# FRONT.net
KiCad netlist of a schematic drawn in Altium Designer
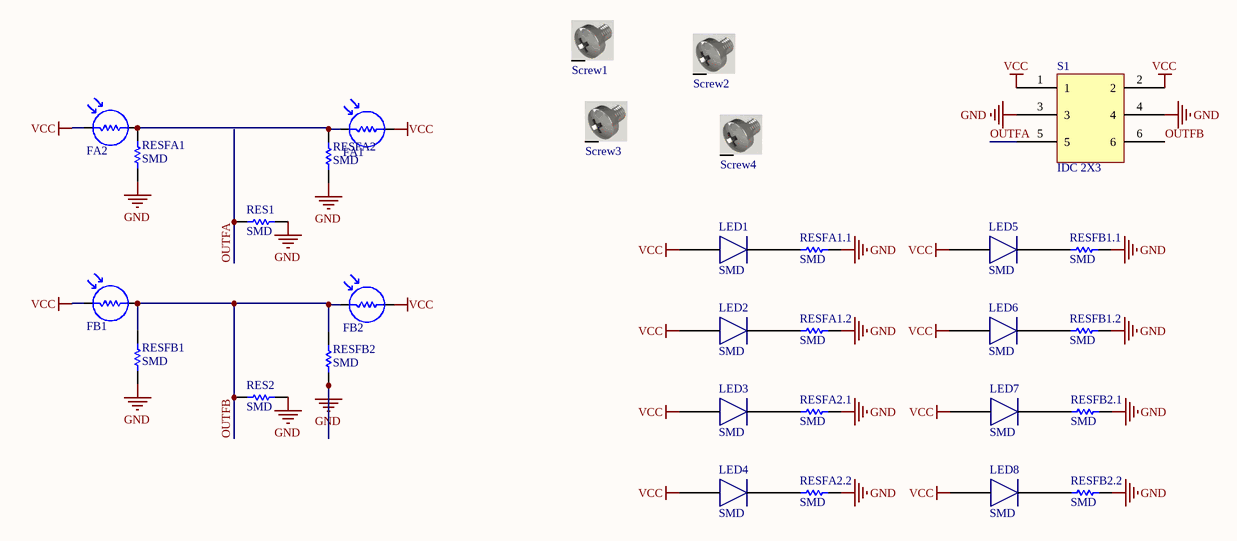
[diagram p0: FRONT.SchDoc]

(export (version "E")
  (design (tool "Eeschema 10.0.6"))
  (components
    (comp (ref "FA1")
      (value "Photo Cell")
      (footprint "PhotoCell.")
      (fields (field (name "PUBLISHER") "Altium Limited"))
      (libsource (lib "Farzanegan") (part "Photo Cell.."))
    )
    (comp (ref "FA2")
      (value "Photo Cell")
      (footprint "PhotoCell.")
      (fields (field (name "PUBLISHER") "Altium Limited"))
      (libsource (lib "Farzanegan") (part "Photo Cell.."))
    )
    (comp (ref "FB1")
      (value "Photo Cell")
      (footprint "PhotoCell.")
      (fields (field (name "PUBLISHER") "Altium Limited"))
      (libsource (lib "Farzanegan") (part "Photo Cell.."))
    )
    (comp (ref "FB2")
      (value "Photo Cell")
      (footprint "PhotoCell.")
      (fields (field (name "PUBLISHER") "Altium Limited"))
      (libsource (lib "Farzanegan") (part "Photo Cell.."))
    )
    (comp (ref "LED1") (value "SMD") (footprint "LED SMD") (libsource (lib "Farzanegan") (part "LED SMD")))
    (comp (ref "LED2") (value "SMD") (footprint "LED SMD") (libsource (lib "Farzanegan") (part "LED SMD")))
    (comp (ref "LED3") (value "SMD") (footprint "LED SMD") (libsource (lib "Farzanegan") (part "LED SMD")))
    (comp (ref "LED4") (value "SMD") (footprint "LED SMD") (libsource (lib "Farzanegan") (part "LED SMD")))
    (comp (ref "LED5") (value "SMD") (footprint "LED SMD") (libsource (lib "Farzanegan") (part "LED SMD")))
    (comp (ref "LED6") (value "SMD") (footprint "LED SMD") (libsource (lib "Farzanegan") (part "LED SMD")))
    (comp (ref "LED7") (value "SMD") (footprint "LED SMD") (libsource (lib "Farzanegan") (part "LED SMD")))
    (comp (ref "LED8") (value "SMD") (footprint "LED SMD") (libsource (lib "Farzanegan") (part "LED SMD")))
    (comp (ref "RES1")
      (value "SMD")
      (footprint "Resistor SMD 1206")
      (libsource (lib "Farzanegan") (part "Res SMD"))
    )
    (comp (ref "RES2")
      (value "SMD")
      (footprint "Resistor SMD 1206")
      (libsource (lib "Farzanegan") (part "Res SMD"))
    )
    (comp (ref "RESFA1")
      (value "SMD")
      (footprint "Resistor SMD 1206")
      (libsource (lib "Farzanegan") (part "Res SMD"))
    )
    (comp (ref "RESFA1.1")
      (value "SMD")
      (footprint "Resistor SMD 1206")
      (libsource (lib "Farzanegan") (part "Res SMD"))
    )
    (comp (ref "RESFA1.2")
      (value "SMD")
      (footprint "Resistor SMD 1206")
      (libsource (lib "Farzanegan") (part "Res SMD"))
    )
    (comp (ref "RESFA2")
      (value "SMD")
      (footprint "Resistor SMD 1206")
      (libsource (lib "Farzanegan") (part "Res SMD"))
    )
    (comp (ref "RESFA2.1")
      (value "SMD")
      (footprint "Resistor SMD 1206")
      (libsource (lib "Farzanegan") (part "Res SMD"))
    )
    (comp (ref "RESFA2.2")
      (value "SMD")
      (footprint "Resistor SMD 1206")
      (libsource (lib "Farzanegan") (part "Res SMD"))
    )
    (comp (ref "RESFB1")
      (value "SMD")
      (footprint "Resistor SMD 1206")
      (libsource (lib "Farzanegan") (part "Res SMD"))
    )
    (comp (ref "RESFB1.1")
      (value "SMD")
      (footprint "Resistor SMD 1206")
      (libsource (lib "Farzanegan") (part "Res SMD"))
    )
    (comp (ref "RESFB1.2")
      (value "SMD")
      (footprint "Resistor SMD 1206")
      (libsource (lib "Farzanegan") (part "Res SMD"))
    )
    (comp (ref "RESFB2")
      (value "SMD")
      (footprint "Resistor SMD 1206")
      (libsource (lib "Farzanegan") (part "Res SMD"))
    )
    (comp (ref "RESFB2.1")
      (value "SMD")
      (footprint "Resistor SMD 1206")
      (libsource (lib "Farzanegan") (part "Res SMD"))
    )
    (comp (ref "RESFB2.2")
      (value "SMD")
      (footprint "Resistor SMD 1206")
      (libsource (lib "Farzanegan") (part "Res SMD"))
    )
    (comp (ref "S1") (value "IDC 2X3") (footprint "IDC 2X3") (libsource (lib "Farzanegan") (part "IDC 2X3")))
    (comp (ref "Screw1")
      (value "Screw")
      (footprint "Screw")
      (fields (field (name "PUBLISHER") "Altium Limited"))
      (libsource (lib "Farzanegan") (part "Screw"))
    )
    (comp (ref "Screw2")
      (value "Screw")
      (footprint "Screw")
      (fields (field (name "PUBLISHER") "Altium Limited"))
      (libsource (lib "Farzanegan") (part "Screw"))
    )
    (comp (ref "Screw3")
      (value "Screw")
      (footprint "Screw")
      (fields (field (name "PUBLISHER") "Altium Limited"))
      (libsource (lib "Farzanegan") (part "Screw"))
    )
    (comp (ref "Screw4")
      (value "Screw")
      (footprint "Screw")
      (fields (field (name "PUBLISHER") "Altium Limited"))
      (libsource (lib "Farzanegan") (part "Screw"))
    )
  )
  (nets
    (net (code "1") (name "/OUTFA") (class "Default")
      (node (ref "RES1") (pin "1") (pinfunction "1_1") (pintype "passive"))
      (node (ref "S1") (pin "5") (pinfunction "5_5") (pintype "passive"))
    )
    (net (code "2") (name "/OUTFB") (class "Default")
      (node (ref "FB1") (pin "2") (pintype "passive"))
      (node (ref "FB2") (pin "1") (pintype "passive"))
      (node (ref "RES2") (pin "1") (pinfunction "1_1") (pintype "passive"))
      (node (ref "RESFB1") (pin "2") (pinfunction "2_2") (pintype "passive"))
      (node (ref "RESFB2") (pin "2") (pinfunction "2_2") (pintype "passive"))
      (node (ref "S1") (pin "6") (pinfunction "6_6") (pintype "passive"))
    )
    (net (code "3") (name "GND") (class "Default")
      (node (ref "RES1") (pin "2") (pinfunction "2_2") (pintype "passive"))
      (node (ref "RES2") (pin "2") (pinfunction "2_2") (pintype "passive"))
      (node (ref "RESFA1") (pin "1") (pinfunction "1_1") (pintype "passive"))
      (node (ref "RESFA1.1") (pin "2") (pinfunction "2_2") (pintype "passive"))
      (node (ref "RESFA1.2") (pin "2") (pinfunction "2_2") (pintype "passive"))
      (node (ref "RESFA2") (pin "1") (pinfunction "1_1") (pintype "passive"))
      (node (ref "RESFA2.1") (pin "2") (pinfunction "2_2") (pintype "passive"))
      (node (ref "RESFA2.2") (pin "2") (pinfunction "2_2") (pintype "passive"))
      (node (ref "RESFB1") (pin "1") (pinfunction "1_1") (pintype "passive"))
      (node (ref "RESFB1.1") (pin "2") (pinfunction "2_2") (pintype "passive"))
      (node (ref "RESFB1.2") (pin "2") (pinfunction "2_2") (pintype "passive"))
      (node (ref "RESFB2") (pin "1") (pinfunction "1_1") (pintype "passive"))
      (node (ref "RESFB2.1") (pin "2") (pinfunction "2_2") (pintype "passive"))
      (node (ref "RESFB2.2") (pin "2") (pinfunction "2_2") (pintype "passive"))
      (node (ref "S1") (pin "3") (pinfunction "3_3") (pintype "passive"))
      (node (ref "S1") (pin "4") (pinfunction "4_4") (pintype "passive"))
    )
    (net (code "4") (name "Net-(FA1-Pad1)") (class "Default")
      (node (ref "FA1") (pin "1") (pintype "passive"))
      (node (ref "FA2") (pin "2") (pintype "passive"))
      (node (ref "RESFA1") (pin "2") (pinfunction "2_2") (pintype "passive"))
      (node (ref "RESFA2") (pin "2") (pinfunction "2_2") (pintype "passive"))
    )
    (net (code "5") (name "Net-(LED1-Pad2)") (class "Default")
      (node (ref "LED1") (pin "2") (pinfunction "2_2") (pintype "passive"))
      (node (ref "RESFA1.1") (pin "1") (pinfunction "1_1") (pintype "passive"))
    )
    (net (code "6") (name "Net-(LED2-Pad2)") (class "Default")
      (node (ref "LED2") (pin "2") (pinfunction "2_2") (pintype "passive"))
      (node (ref "RESFA1.2") (pin "1") (pinfunction "1_1") (pintype "passive"))
    )
    (net (code "7") (name "Net-(LED3-Pad2)") (class "Default")
      (node (ref "LED3") (pin "2") (pinfunction "2_2") (pintype "passive"))
      (node (ref "RESFA2.1") (pin "1") (pinfunction "1_1") (pintype "passive"))
    )
    (net (code "8") (name "Net-(LED4-Pad2)") (class "Default")
      (node (ref "LED4") (pin "2") (pinfunction "2_2") (pintype "passive"))
      (node (ref "RESFA2.2") (pin "1") (pinfunction "1_1") (pintype "passive"))
    )
    (net (code "9") (name "Net-(LED5-Pad2)") (class "Default")
      (node (ref "LED5") (pin "2") (pinfunction "2_2") (pintype "passive"))
      (node (ref "RESFB1.1") (pin "1") (pinfunction "1_1") (pintype "passive"))
    )
    (net (code "10") (name "Net-(LED6-Pad2)") (class "Default")
      (node (ref "LED6") (pin "2") (pinfunction "2_2") (pintype "passive"))
      (node (ref "RESFB1.2") (pin "1") (pinfunction "1_1") (pintype "passive"))
    )
    (net (code "11") (name "Net-(LED7-Pad2)") (class "Default")
      (node (ref "LED7") (pin "2") (pinfunction "2_2") (pintype "passive"))
      (node (ref "RESFB2.1") (pin "1") (pinfunction "1_1") (pintype "passive"))
    )
    (net (code "12") (name "Net-(LED8-Pad2)") (class "Default")
      (node (ref "LED8") (pin "2") (pinfunction "2_2") (pintype "passive"))
      (node (ref "RESFB2.2") (pin "1") (pinfunction "1_1") (pintype "passive"))
    )
    (net (code "13") (name "VCC") (class "Default")
      (node (ref "FA1") (pin "2") (pintype "passive"))
      (node (ref "FA2") (pin "1") (pintype "passive"))
      (node (ref "FB1") (pin "1") (pintype "passive"))
      (node (ref "FB2") (pin "2") (pintype "passive"))
      (node (ref "LED1") (pin "1") (pinfunction "1_1") (pintype "passive"))
      (node (ref "LED2") (pin "1") (pinfunction "1_1") (pintype "passive"))
      (node (ref "LED3") (pin "1") (pinfunction "1_1") (pintype "passive"))
      (node (ref "LED4") (pin "1") (pinfunction "1_1") (pintype "passive"))
      (node (ref "LED5") (pin "1") (pinfunction "1_1") (pintype "passive"))
      (node (ref "LED6") (pin "1") (pinfunction "1_1") (pintype "passive"))
      (node (ref "LED7") (pin "1") (pinfunction "1_1") (pintype "passive"))
      (node (ref "LED8") (pin "1") (pinfunction "1_1") (pintype "passive"))
      (node (ref "S1") (pin "1") (pinfunction "1_1") (pintype "passive"))
      (node (ref "S1") (pin "2") (pinfunction "2_2") (pintype "passive"))
    )
    (net (code "14") (name "unconnected-(Screw1-PadS)") (class "Default")
      (node (ref "Screw1") (pin "S") (pinfunction "S_S") (pintype "passive"))
    )
    (net (code "15") (name "unconnected-(Screw2-PadS)") (class "Default")
      (node (ref "Screw2") (pin "S") (pinfunction "S_S") (pintype "passive"))
    )
    (net (code "16") (name "unconnected-(Screw3-PadS)") (class "Default")
      (node (ref "Screw3") (pin "S") (pinfunction "S_S") (pintype "passive"))
    )
    (net (code "17") (name "unconnected-(Screw4-PadS)") (class "Default")
      (node (ref "Screw4") (pin "S") (pinfunction "S_S") (pintype "passive"))
    )
  )
)
